# motor_driver.net
KiCad netlist of a schematic drawn in EAGLE
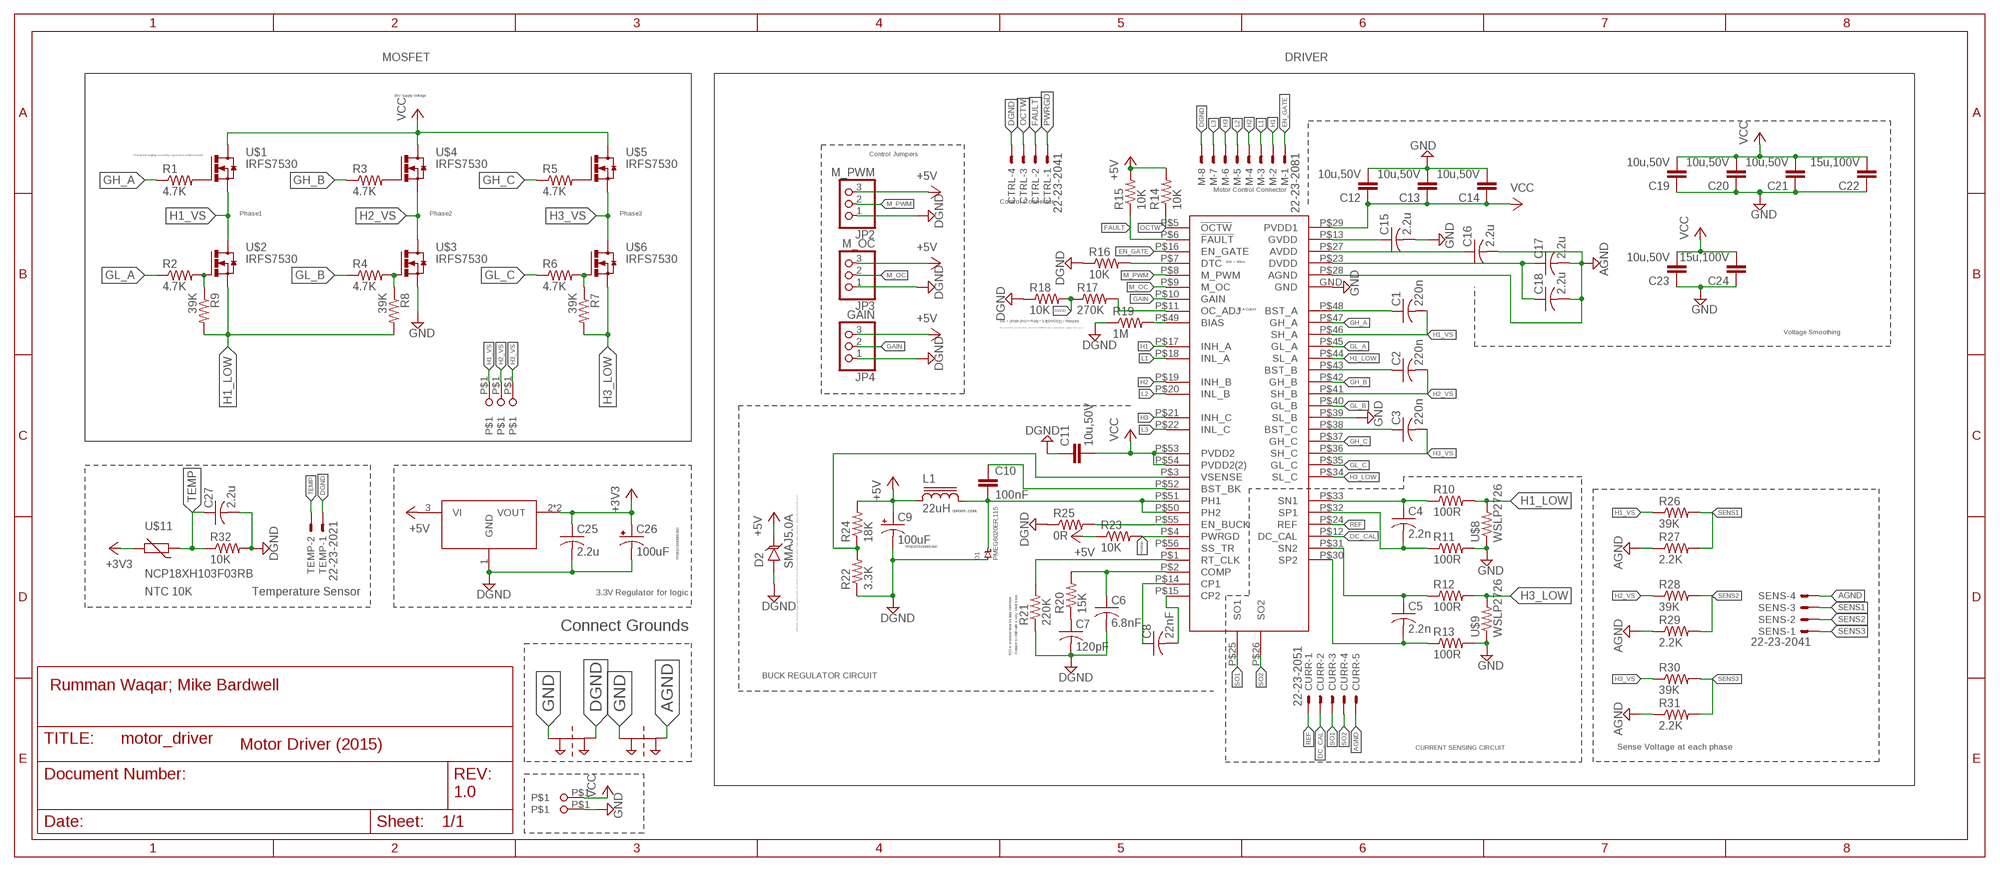
[diagram p0: schematic, sheet 1]

(export (version "E")
  (design (tool "Eeschema 10.0.6"))
  (components
    (comp (ref "C1")
      (value "220n")
      (footprint "eagle-import:C0805")
      (libsource (lib "eagle-import") (part "C-USC0805"))
    )
    (comp (ref "C2")
      (value "220n")
      (footprint "eagle-import:C0805")
      (libsource (lib "eagle-import") (part "C-USC0805"))
    )
    (comp (ref "C3")
      (value "220n")
      (footprint "eagle-import:C0805")
      (libsource (lib "eagle-import") (part "C-USC0805"))
    )
    (comp (ref "C4")
      (value "2.2n")
      (footprint "eagle-import:C0603")
      (libsource (lib "eagle-import") (part "C-USC0603"))
    )
    (comp (ref "C5")
      (value "2.2n")
      (footprint "eagle-import:C0603")
      (libsource (lib "eagle-import") (part "C-USC0603"))
    )
    (comp (ref "C6")
      (value "6.8nF")
      (footprint "eagle-import:C0603")
      (libsource (lib "eagle-import") (part "C-USC0603"))
    )
    (comp (ref "C7")
      (value "120pF")
      (footprint "eagle-import:C0603")
      (libsource (lib "eagle-import") (part "C-USC0603"))
    )
    (comp (ref "C8")
      (value "22nF")
      (footprint "eagle-import:C0603")
      (libsource (lib "eagle-import") (part "C-USC0603"))
    )
    (comp (ref "C9")
      (value "100uF")
      (footprint "eagle-import:EIA3528-KIT")
      (libsource (lib "eagle-import") (part "CAP_POL3528-KIT"))
    )
    (comp (ref "C10")
      (value "100nF")
      (footprint "eagle-import:0805")
      (libsource (lib "eagle-import") (part "CAP0805"))
    )
    (comp (ref "C11")
      (value "10u,50V")
      (footprint "eagle-import:1206")
      (libsource (lib "eagle-import") (part "CAP1206"))
    )
    (comp (ref "C12")
      (value "10u,50V")
      (footprint "eagle-import:1206")
      (libsource (lib "eagle-import") (part "CAP1206"))
    )
    (comp (ref "C13")
      (value "10u,50V")
      (footprint "eagle-import:1206")
      (libsource (lib "eagle-import") (part "CAP1206"))
    )
    (comp (ref "C14")
      (value "10u,50V")
      (footprint "eagle-import:1206")
      (libsource (lib "eagle-import") (part "CAP1206"))
    )
    (comp (ref "C15")
      (value "2.2u")
      (footprint "eagle-import:C0805")
      (libsource (lib "eagle-import") (part "C-USC0805"))
    )
    (comp (ref "C16")
      (value "2.2u")
      (footprint "eagle-import:C0805")
      (libsource (lib "eagle-import") (part "C-USC0805"))
    )
    (comp (ref "C17")
      (value "2.2u")
      (footprint "eagle-import:C0805")
      (libsource (lib "eagle-import") (part "C-USC0805"))
    )
    (comp (ref "C18")
      (value "2.2u")
      (footprint "eagle-import:C0805")
      (libsource (lib "eagle-import") (part "C-USC0805"))
    )
    (comp (ref "C19")
      (value "10u,50V")
      (footprint "eagle-import:1206")
      (libsource (lib "eagle-import") (part "CAP1206"))
    )
    (comp (ref "C20")
      (value "10u,50V")
      (footprint "eagle-import:1206")
      (libsource (lib "eagle-import") (part "CAP1206"))
    )
    (comp (ref "C21")
      (value "10u,50V")
      (footprint "eagle-import:1206")
      (libsource (lib "eagle-import") (part "CAP1206"))
    )
    (comp (ref "C22")
      (value "15u,100V")
      (footprint "eagle-import:C2220K")
      (libsource (lib "eagle-import") (part "C-EUC2220K"))
    )
    (comp (ref "C23")
      (value "10u,50V")
      (footprint "eagle-import:1206")
      (libsource (lib "eagle-import") (part "CAP1206"))
    )
    (comp (ref "C24")
      (value "15u,100V")
      (footprint "eagle-import:C2220K")
      (libsource (lib "eagle-import") (part "C-EUC2220K"))
    )
    (comp (ref "C25")
      (value "2.2u")
      (footprint "eagle-import:C0805")
      (libsource (lib "eagle-import") (part "C-USC0805"))
    )
    (comp (ref "C26")
      (value "100uF")
      (footprint "eagle-import:EIA3528-KIT")
      (libsource (lib "eagle-import") (part "CAP_POL3528-KIT"))
    )
    (comp (ref "C27")
      (value "2.2u")
      (footprint "eagle-import:C0805")
      (libsource (lib "eagle-import") (part "C-USC0805"))
    )
    (comp (ref "CTRL")
      (value "22-23-2041")
      (footprint "eagle-import:22-23-2041")
      (fields (field (name "MF") "MOLEX"))
      (libsource (lib "eagle-import") (part "22-23-2041"))
    )
    (comp (ref "CURR")
      (value "22-23-2051")
      (footprint "eagle-import:22-23-2051")
      (fields (field (name "MF") "MOLEX"))
      (libsource (lib "eagle-import") (part "22-23-2051"))
    )
    (comp (ref "D1")
      (value "PMEG6020ER,115")
      (footprint "eagle-import:SOD123W")
      (libsource (lib "eagle-import") (part "DIODE[SCHOTKY]-SOD123W"))
    )
    (comp (ref "D2")
      (value "SMAJ5.0A")
      (footprint "eagle-import:SMA-DIODE")
      (libsource (lib "eagle-import") (part "TVSSMA"))
    )
    (comp (ref "JP2")
      (value "M_PWM")
      (footprint "eagle-import:1X03")
      (libsource (lib "eagle-import") (part "PINHD-1X3"))
    )
    (comp (ref "JP3")
      (value "M_OC")
      (footprint "eagle-import:1X03")
      (libsource (lib "eagle-import") (part "PINHD-1X3"))
    )
    (comp (ref "JP4")
      (value "GAIN")
      (footprint "eagle-import:1X03")
      (libsource (lib "eagle-import") (part "PINHD-1X3"))
    )
    (comp (ref "L1")
      (value "22uH")
      (footprint "eagle-import:SDR0805")
      (libsource (lib "eagle-import") (part "SDR0805"))
    )
    (comp (ref "M")
      (value "22-23-2081")
      (footprint "eagle-import:22-23-2081")
      (fields (field (name "MF") "MOLEX"))
      (libsource (lib "eagle-import") (part "22-23-2081"))
    )
    (comp (ref "PT1")
      (value "2PT_GND_TIE")
      (footprint "eagle-import:2PT_GND_TIE")
      (libsource (lib "eagle-import") (part "2PT_GND_TIE"))
    )
    (comp (ref "PT2")
      (value "2PT_GND_TIE")
      (footprint "eagle-import:2PT_GND_TIE")
      (libsource (lib "eagle-import") (part "2PT_GND_TIE"))
    )
    (comp (ref "R1")
      (value "4.7K")
      (footprint "eagle-import:R0603")
      (libsource (lib "eagle-import") (part "R-US_R0603"))
    )
    (comp (ref "R2")
      (value "4.7K")
      (footprint "eagle-import:R0603")
      (libsource (lib "eagle-import") (part "R-US_R0603"))
    )
    (comp (ref "R3")
      (value "4.7K")
      (footprint "eagle-import:R0603")
      (libsource (lib "eagle-import") (part "R-US_R0603"))
    )
    (comp (ref "R4")
      (value "4.7K")
      (footprint "eagle-import:R0603")
      (libsource (lib "eagle-import") (part "R-US_R0603"))
    )
    (comp (ref "R5")
      (value "4.7K")
      (footprint "eagle-import:R0603")
      (libsource (lib "eagle-import") (part "R-US_R0603"))
    )
    (comp (ref "R6")
      (value "4.7K")
      (footprint "eagle-import:R0603")
      (libsource (lib "eagle-import") (part "R-US_R0603"))
    )
    (comp (ref "R7")
      (value "39K")
      (footprint "eagle-import:R0603")
      (libsource (lib "eagle-import") (part "R-US_R0603"))
    )
    (comp (ref "R8")
      (value "39K")
      (footprint "eagle-import:R0603")
      (libsource (lib "eagle-import") (part "R-US_R0603"))
    )
    (comp (ref "R9")
      (value "39K")
      (footprint "eagle-import:R0603")
      (libsource (lib "eagle-import") (part "R-US_R0603"))
    )
    (comp (ref "R10")
      (value "100R")
      (footprint "eagle-import:R0603")
      (libsource (lib "eagle-import") (part "R-US_R0603"))
    )
    (comp (ref "R11")
      (value "100R")
      (footprint "eagle-import:R0603")
      (libsource (lib "eagle-import") (part "R-US_R0603"))
    )
    (comp (ref "R12")
      (value "100R")
      (footprint "eagle-import:R0603")
      (libsource (lib "eagle-import") (part "R-US_R0603"))
    )
    (comp (ref "R13")
      (value "100R")
      (footprint "eagle-import:R0603")
      (libsource (lib "eagle-import") (part "R-US_R0603"))
    )
    (comp (ref "R14")
      (value "10K")
      (footprint "eagle-import:R0603")
      (libsource (lib "eagle-import") (part "R-US_R0603"))
    )
    (comp (ref "R15")
      (value "10K")
      (footprint "eagle-import:R0603")
      (libsource (lib "eagle-import") (part "R-US_R0603"))
    )
    (comp (ref "R16")
      (value "10K")
      (footprint "eagle-import:R0603")
      (libsource (lib "eagle-import") (part "R-US_R0603"))
    )
    (comp (ref "R17")
      (value "270K")
      (footprint "eagle-import:R0603")
      (libsource (lib "eagle-import") (part "R-US_R0603"))
    )
    (comp (ref "R18")
      (value "10K")
      (footprint "eagle-import:R0603")
      (libsource (lib "eagle-import") (part "R-US_R0603"))
    )
    (comp (ref "R19")
      (value "1M")
      (footprint "eagle-import:R0603")
      (libsource (lib "eagle-import") (part "R-US_R0603"))
    )
    (comp (ref "R20")
      (value "15K")
      (footprint "eagle-import:R0603")
      (libsource (lib "eagle-import") (part "R-US_R0603"))
    )
    (comp (ref "R21")
      (value "220K")
      (footprint "eagle-import:R0603")
      (libsource (lib "eagle-import") (part "R-US_R0603"))
    )
    (comp (ref "R22")
      (value "3.3K")
      (footprint "eagle-import:R0603")
      (libsource (lib "eagle-import") (part "R-US_R0603"))
    )
    (comp (ref "R23")
      (value "10K")
      (footprint "eagle-import:R0603")
      (libsource (lib "eagle-import") (part "R-US_R0603"))
    )
    (comp (ref "R24")
      (value "18K")
      (footprint "eagle-import:R0603")
      (libsource (lib "eagle-import") (part "R-US_R0603"))
    )
    (comp (ref "R25")
      (value "0R")
      (footprint "eagle-import:R0603")
      (libsource (lib "eagle-import") (part "R-US_R0603"))
    )
    (comp (ref "R26")
      (value "39K")
      (footprint "eagle-import:R0805")
      (libsource (lib "eagle-import") (part "R-US_R0805"))
    )
    (comp (ref "R27")
      (value "2.2K")
      (footprint "eagle-import:R0805")
      (libsource (lib "eagle-import") (part "R-US_R0805"))
    )
    (comp (ref "R28")
      (value "39K")
      (footprint "eagle-import:R0805")
      (libsource (lib "eagle-import") (part "R-US_R0805"))
    )
    (comp (ref "R29")
      (value "2.2K")
      (footprint "eagle-import:R0805")
      (libsource (lib "eagle-import") (part "R-US_R0805"))
    )
    (comp (ref "R30")
      (value "39K")
      (footprint "eagle-import:R0805")
      (libsource (lib "eagle-import") (part "R-US_R0805"))
    )
    (comp (ref "R31")
      (value "2.2K")
      (footprint "eagle-import:R0805")
      (libsource (lib "eagle-import") (part "R-US_R0805"))
    )
    (comp (ref "R32")
      (value "10K")
      (footprint "eagle-import:M0805")
      (libsource (lib "eagle-import") (part "R-US_M0805"))
    )
    (comp (ref "SENS")
      (value "22-23-2041")
      (footprint "eagle-import:22-23-2041")
      (fields (field (name "MF") "MOLEX"))
      (libsource (lib "eagle-import") (part "22-23-2041"))
    )
    (comp (ref "TEMP")
      (value "22-23-2021")
      (footprint "eagle-import:22-23-2021")
      (fields (field (name "MF") "MOLEX"))
      (libsource (lib "eagle-import") (part "22-23-2021"))
    )
    (comp (ref "U$1")
      (value "IRFS7530")
      (footprint "eagle-import:IRF7530_HEATSINK")
      (libsource (lib "eagle-import") (part "IRFS7530_HEATSINK"))
    )
    (comp (ref "U$2")
      (value "IRFS7530")
      (footprint "eagle-import:IRF7530_HEATSINK")
      (libsource (lib "eagle-import") (part "IRFS7530_HEATSINK"))
    )
    (comp (ref "U$3")
      (value "IRFS7530")
      (footprint "eagle-import:IRF7530_HEATSINK")
      (libsource (lib "eagle-import") (part "IRFS7530_HEATSINK"))
    )
    (comp (ref "U$4")
      (value "IRFS7530")
      (footprint "eagle-import:IRF7530_HEATSINK")
      (libsource (lib "eagle-import") (part "IRFS7530_HEATSINK"))
    )
    (comp (ref "U$5")
      (value "IRFS7530")
      (footprint "eagle-import:IRF7530_HEATSINK")
      (libsource (lib "eagle-import") (part "IRFS7530_HEATSINK"))
    )
    (comp (ref "U$6")
      (value "IRFS7530")
      (footprint "eagle-import:IRF7530_HEATSINK")
      (libsource (lib "eagle-import") (part "IRFS7530_HEATSINK"))
    )
    (comp (ref "U$7")
      (value "DRV8302")
      (footprint "eagle-import:DRV8302")
      (libsource (lib "eagle-import") (part "DRV8302"))
    )
    (comp (ref "U$8")
      (value "WSLP2726")
      (footprint "eagle-import:WSLP2726")
      (libsource (lib "eagle-import") (part "WSLP2726"))
    )
    (comp (ref "U$9")
      (value "WSLP2726")
      (footprint "eagle-import:WSLP2726")
      (libsource (lib "eagle-import") (part "WSLP2726"))
    )
    (comp (ref "U$10")
      (value "TC2117")
      (footprint "eagle-import:SOT223")
      (libsource (lib "eagle-import") (part "TC2117"))
    )
    (comp (ref "U$11")
      (value "NCP18XH103F03RB")
      (footprint "eagle-import:R0603")
      (libsource (lib "eagle-import") (part "NCP18XH103F03RB"))
    )
    (comp (ref "U$12")
      (value "1CONN_SOLDER")
      (footprint "eagle-import:1CONN_PAD")
      (libsource (lib "eagle-import") (part "1CONN_SOLDER"))
    )
    (comp (ref "U$13")
      (value "1CONN_SOLDER")
      (footprint "eagle-import:1CONN_PAD")
      (libsource (lib "eagle-import") (part "1CONN_SOLDER"))
    )
    (comp (ref "U$14")
      (value "1CONN_SOLDER")
      (footprint "eagle-import:1CONN_PAD")
      (libsource (lib "eagle-import") (part "1CONN_SOLDER"))
    )
    (comp (ref "U$15")
      (value "1CONN_SOLDER")
      (footprint "eagle-import:1CONN_PAD")
      (libsource (lib "eagle-import") (part "1CONN_SOLDER"))
    )
    (comp (ref "U$16")
      (value "1CONN_SOLDER")
      (footprint "eagle-import:1CONN_PAD")
      (libsource (lib "eagle-import") (part "1CONN_SOLDER"))
    )
  )
  (nets
    (net (code "1") (name "+3V3") (class "Default")
      (node (ref "C25") (pin "1") (pinfunction "1_1") (pintype "passive"))
      (node (ref "C26") (pin "A") (pinfunction "+_A") (pintype "passive"))
      (node (ref "U$10") (pin "2") (pinfunction "VOUT_2") (pintype "bidirectional"))
      (node (ref "U$10") (pin "4") (pinfunction "VOUT_4") (pintype "bidirectional"))
      (node (ref "U$11") (pin "2") (pinfunction "2_2") (pintype "passive"))
    )
    (net (code "2") (name "+5V") (class "Default")
      (node (ref "C9") (pin "A") (pinfunction "+_A") (pintype "passive"))
      (node (ref "D2") (pin "C") (pinfunction "C_C") (pintype "passive"))
      (node (ref "JP2") (pin "3") (pinfunction "3_3") (pintype "passive"))
      (node (ref "JP3") (pin "3") (pinfunction "3_3") (pintype "passive"))
      (node (ref "JP4") (pin "3") (pinfunction "3_3") (pintype "passive"))
      (node (ref "L1") (pin "1") (pinfunction "1_1") (pintype "passive"))
      (node (ref "R14") (pin "2") (pinfunction "2_2") (pintype "passive"))
      (node (ref "R15") (pin "2") (pinfunction "2_2") (pintype "passive"))
      (node (ref "R23") (pin "1") (pinfunction "1_1") (pintype "passive"))
      (node (ref "R24") (pin "2") (pinfunction "2_2") (pintype "passive"))
      (node (ref "U$10") (pin "3") (pinfunction "VI_3") (pintype "bidirectional"))
    )
    (net (code "3") (name "AGND") (class "Default")
      (node (ref "C16") (pin "2") (pinfunction "2_2") (pintype "passive"))
      (node (ref "C17") (pin "2") (pinfunction "2_2") (pintype "passive"))
      (node (ref "C18") (pin "2") (pinfunction "2_2") (pintype "passive"))
      (node (ref "CURR") (pin "5") (pinfunction "S_5") (pintype "passive"))
      (node (ref "PT2") (pin "P$2") (pinfunction "P$2_P$2") (pintype "bidirectional"))
      (node (ref "R27") (pin "1") (pinfunction "1_1") (pintype "passive"))
      (node (ref "R29") (pin "1") (pinfunction "1_1") (pintype "passive"))
      (node (ref "R31") (pin "1") (pinfunction "1_1") (pintype "passive"))
      (node (ref "SENS") (pin "4") (pinfunction "S_4") (pintype "passive"))
      (node (ref "U$7") (pin "P$28") (pinfunction "AGND_P$28") (pintype "bidirectional"))
    )
    (net (code "4") (name "DC_CAL") (class "Default")
      (node (ref "CURR") (pin "2") (pinfunction "S_2") (pintype "passive"))
      (node (ref "U$7") (pin "P$12") (pinfunction "DC_CAL_P$12") (pintype "bidirectional"))
    )
    (net (code "5") (name "DGND") (class "Default")
      (node (ref "C11") (pin "1") (pinfunction "1_1") (pintype "passive"))
      (node (ref "C25") (pin "2") (pinfunction "2_2") (pintype "passive"))
      (node (ref "C26") (pin "C") (pinfunction "-_C") (pintype "passive"))
      (node (ref "C27") (pin "2") (pinfunction "2_2") (pintype "passive"))
      (node (ref "C6") (pin "2") (pinfunction "2_2") (pintype "passive"))
      (node (ref "C7") (pin "2") (pinfunction "2_2") (pintype "passive"))
      (node (ref "C9") (pin "C") (pinfunction "-_C") (pintype "passive"))
      (node (ref "CTRL") (pin "4") (pinfunction "S_4") (pintype "passive"))
      (node (ref "D1") (pin "P$1") (pinfunction "1_P$1") (pintype "bidirectional"))
      (node (ref "D2") (pin "A") (pinfunction "A_A") (pintype "passive"))
      (node (ref "JP2") (pin "1") (pinfunction "1_1") (pintype "passive"))
      (node (ref "JP3") (pin "1") (pinfunction "1_1") (pintype "passive"))
      (node (ref "JP4") (pin "1") (pinfunction "1_1") (pintype "passive"))
      (node (ref "M") (pin "8") (pinfunction "S_8") (pintype "passive"))
      (node (ref "PT1") (pin "P$2") (pinfunction "P$2_P$2") (pintype "bidirectional"))
      (node (ref "R16") (pin "1") (pinfunction "1_1") (pintype "passive"))
      (node (ref "R18") (pin "1") (pinfunction "1_1") (pintype "passive"))
      (node (ref "R19") (pin "1") (pinfunction "1_1") (pintype "passive"))
      (node (ref "R21") (pin "1") (pinfunction "1_1") (pintype "passive"))
      (node (ref "R22") (pin "1") (pinfunction "1_1") (pintype "passive"))
      (node (ref "R25") (pin "1") (pinfunction "1_1") (pintype "passive"))
      (node (ref "R32") (pin "2") (pinfunction "2_2") (pintype "passive"))
      (node (ref "TEMP") (pin "1") (pinfunction "S_1") (pintype "passive"))
      (node (ref "U$10") (pin "1") (pinfunction "GND_1") (pintype "bidirectional"))
    )
    (net (code "6") (name "DVDD") (class "Default")
      (node (ref "R17") (pin "1") (pinfunction "1_1") (pintype "passive"))
      (node (ref "R18") (pin "2") (pinfunction "2_2") (pintype "passive"))
    )
    (net (code "7") (name "EN_GATE") (class "Default")
      (node (ref "M") (pin "1") (pinfunction "S_1") (pintype "passive"))
      (node (ref "U$7") (pin "P$16") (pinfunction "EN_GATE_P$16") (pintype "bidirectional"))
    )
    (net (code "8") (name "FAULT") (class "Default")
      (node (ref "CTRL") (pin "2") (pinfunction "S_2") (pintype "passive"))
      (node (ref "R15") (pin "1") (pinfunction "1_1") (pintype "passive"))
      (node (ref "U$7") (pin "P$6") (pinfunction "~{FAULT}_P$6") (pintype "bidirectional"))
    )
    (net (code "9") (name "GAIN") (class "Default")
      (node (ref "JP4") (pin "2") (pinfunction "2_2") (pintype "passive"))
      (node (ref "U$7") (pin "P$10") (pinfunction "GAIN_P$10") (pintype "bidirectional"))
    )
    (net (code "10") (name "GH_A") (class "Default")
      (node (ref "R1") (pin "1") (pinfunction "1_1") (pintype "passive"))
      (node (ref "U$7") (pin "P$47") (pinfunction "GH_A_P$47") (pintype "bidirectional"))
    )
    (net (code "11") (name "GH_B") (class "Default")
      (node (ref "R3") (pin "1") (pinfunction "1_1") (pintype "passive"))
      (node (ref "U$7") (pin "P$42") (pinfunction "GH_B_P$42") (pintype "bidirectional"))
    )
    (net (code "12") (name "GH_C") (class "Default")
      (node (ref "R5") (pin "1") (pinfunction "1_1") (pintype "passive"))
      (node (ref "U$7") (pin "P$37") (pinfunction "GH_C_P$37") (pintype "bidirectional"))
    )
    (net (code "13") (name "GL_A") (class "Default")
      (node (ref "R2") (pin "1") (pinfunction "1_1") (pintype "passive"))
      (node (ref "U$7") (pin "P$45") (pinfunction "GL_A_P$45") (pintype "bidirectional"))
    )
    (net (code "14") (name "GL_B") (class "Default")
      (node (ref "R4") (pin "1") (pinfunction "1_1") (pintype "passive"))
      (node (ref "U$7") (pin "P$40") (pinfunction "GL_B_P$40") (pintype "bidirectional"))
    )
    (net (code "15") (name "GL_C") (class "Default")
      (node (ref "R6") (pin "1") (pinfunction "1_1") (pintype "passive"))
      (node (ref "U$7") (pin "P$35") (pinfunction "GL_C_P$35") (pintype "bidirectional"))
    )
    (net (code "16") (name "GND") (class "Default")
      (node (ref "C12") (pin "2") (pinfunction "2_2") (pintype "passive"))
      (node (ref "C13") (pin "2") (pinfunction "2_2") (pintype "passive"))
      (node (ref "C14") (pin "2") (pinfunction "2_2") (pintype "passive"))
      (node (ref "C15") (pin "2") (pinfunction "2_2") (pintype "passive"))
      (node (ref "C19") (pin "1") (pinfunction "1_1") (pintype "passive"))
      (node (ref "C20") (pin "1") (pinfunction "1_1") (pintype "passive"))
      (node (ref "C21") (pin "1") (pinfunction "1_1") (pintype "passive"))
      (node (ref "C22") (pin "1") (pinfunction "1_1") (pintype "passive"))
      (node (ref "C23") (pin "1") (pinfunction "1_1") (pintype "passive"))
      (node (ref "C24") (pin "1") (pinfunction "1_1") (pintype "passive"))
      (node (ref "PT1") (pin "P$1") (pinfunction "P$1_P$1") (pintype "bidirectional"))
      (node (ref "PT2") (pin "P$1") (pinfunction "P$1_P$1") (pintype "bidirectional"))
      (node (ref "R11") (pin "2") (pinfunction "2_2") (pintype "passive"))
      (node (ref "R13") (pin "2") (pinfunction "2_2") (pintype "passive"))
      (node (ref "U$16") (pin "P$1") (pinfunction "P$1_P$1") (pintype "bidirectional"))
      (node (ref "U$3") (pin "S1") (pinfunction "S_S1") (pintype "passive"))
      (node (ref "U$3") (pin "S2") (pinfunction "S_S2") (pintype "passive"))
      (node (ref "U$3") (pin "S3") (pinfunction "S_S3") (pintype "passive"))
      (node (ref "U$3") (pin "S4") (pinfunction "S_S4") (pintype "passive"))
      (node (ref "U$3") (pin "S5") (pinfunction "S_S5") (pintype "passive"))
      (node (ref "U$7") (pin "GND") (pinfunction "GND_GND") (pintype "bidirectional"))
      (node (ref "U$7") (pin "P$39") (pinfunction "SL_B_P$39") (pintype "bidirectional"))
      (node (ref "U$8") (pin "P$1@1") (pinfunction "1_P$1@1") (pintype "passive"))
      (node (ref "U$8") (pin "P$1@2") (pinfunction "1_P$1@2") (pintype "passive"))
      (node (ref "U$9") (pin "P$1@1") (pinfunction "1_P$1@1") (pintype "passive"))
      (node (ref "U$9") (pin "P$1@2") (pinfunction "1_P$1@2") (pintype "passive"))
    )
    (net (code "17") (name "H1") (class "Default")
      (node (ref "M") (pin "2") (pinfunction "S_2") (pintype "passive"))
      (node (ref "U$7") (pin "P$17") (pinfunction "INH_A_P$17") (pintype "bidirectional"))
    )
    (net (code "18") (name "H1_LOW") (class "Default")
      (node (ref "R10") (pin "2") (pinfunction "2_2") (pintype "passive"))
      (node (ref "R8") (pin "2") (pinfunction "2_2") (pintype "passive"))
      (node (ref "R9") (pin "2") (pinfunction "2_2") (pintype "passive"))
      (node (ref "U$2") (pin "S1") (pinfunction "S_S1") (pintype "passive"))
      (node (ref "U$2") (pin "S2") (pinfunction "S_S2") (pintype "passive"))
      (node (ref "U$2") (pin "S3") (pinfunction "S_S3") (pintype "passive"))
      (node (ref "U$2") (pin "S4") (pinfunction "S_S4") (pintype "passive"))
      (node (ref "U$2") (pin "S5") (pinfunction "S_S5") (pintype "passive"))
      (node (ref "U$7") (pin "P$44") (pinfunction "SL_A_P$44") (pintype "bidirectional"))
      (node (ref "U$8") (pin "P$2@1") (pinfunction "2_P$2@1") (pintype "passive"))
      (node (ref "U$8") (pin "P$2@2") (pinfunction "2_P$2@2") (pintype "passive"))
    )
    (net (code "19") (name "H1_VS") (class "Default")
      (node (ref "C1") (pin "2") (pinfunction "2_2") (pintype "passive"))
      (node (ref "R26") (pin "1") (pinfunction "1_1") (pintype "passive"))
      (node (ref "U$1") (pin "S1") (pinfunction "S_S1") (pintype "passive"))
      (node (ref "U$1") (pin "S2") (pinfunction "S_S2") (pintype "passive"))
      (node (ref "U$1") (pin "S3") (pinfunction "S_S3") (pintype "passive"))
      (node (ref "U$1") (pin "S4") (pinfunction "S_S4") (pintype "passive"))
      (node (ref "U$1") (pin "S5") (pinfunction "S_S5") (pintype "passive"))
      (node (ref "U$14") (pin "P$1") (pinfunction "P$1_P$1") (pintype "bidirectional"))
      (node (ref "U$2") (pin "D1") (pinfunction "D_D1") (pintype "passive"))
      (node (ref "U$7") (pin "P$46") (pinfunction "SH_A_P$46") (pintype "bidirectional"))
    )
    (net (code "20") (name "H2") (class "Default")
      (node (ref "M") (pin "4") (pinfunction "S_4") (pintype "passive"))
      (node (ref "U$7") (pin "P$19") (pinfunction "INH_B_P$19") (pintype "bidirectional"))
    )
    (net (code "21") (name "H2_VS") (class "Default")
      (node (ref "C2") (pin "2") (pinfunction "2_2") (pintype "passive"))
      (node (ref "R28") (pin "1") (pinfunction "1_1") (pintype "passive"))
      (node (ref "U$13") (pin "P$1") (pinfunction "P$1_P$1") (pintype "bidirectional"))
      (node (ref "U$3") (pin "D1") (pinfunction "D_D1") (pintype "passive"))
      (node (ref "U$4") (pin "S1") (pinfunction "S_S1") (pintype "passive"))
      (node (ref "U$4") (pin "S2") (pinfunction "S_S2") (pintype "passive"))
      (node (ref "U$4") (pin "S3") (pinfunction "S_S3") (pintype "passive"))
      (node (ref "U$4") (pin "S4") (pinfunction "S_S4") (pintype "passive"))
      (node (ref "U$4") (pin "S5") (pinfunction "S_S5") (pintype "passive"))
      (node (ref "U$7") (pin "P$41") (pinfunction "SH_B_P$41") (pintype "bidirectional"))
    )
    (net (code "22") (name "H3") (class "Default")
      (node (ref "M") (pin "6") (pinfunction "S_6") (pintype "passive"))
      (node (ref "U$7") (pin "P$21") (pinfunction "INH_C_P$21") (pintype "bidirectional"))
    )
    (net (code "23") (name "H3_LOW") (class "Default")
      (node (ref "R12") (pin "2") (pinfunction "2_2") (pintype "passive"))
      (node (ref "R7") (pin "2") (pinfunction "2_2") (pintype "passive"))
      (node (ref "U$6") (pin "S1") (pinfunction "S_S1") (pintype "passive"))
      (node (ref "U$6") (pin "S2") (pinfunction "S_S2") (pintype "passive"))
      (node (ref "U$6") (pin "S3") (pinfunction "S_S3") (pintype "passive"))
      (node (ref "U$6") (pin "S4") (pinfunction "S_S4") (pintype "passive"))
      (node (ref "U$6") (pin "S5") (pinfunction "S_S5") (pintype "passive"))
      (node (ref "U$7") (pin "P$34") (pinfunction "SL_C_P$34") (pintype "bidirectional"))
      (node (ref "U$9") (pin "P$2@1") (pinfunction "2_P$2@1") (pintype "passive"))
      (node (ref "U$9") (pin "P$2@2") (pinfunction "2_P$2@2") (pintype "passive"))
    )
    (net (code "24") (name "H3_VS") (class "Default")
      (node (ref "C3") (pin "2") (pinfunction "2_2") (pintype "passive"))
      (node (ref "R30") (pin "1") (pinfunction "1_1") (pintype "passive"))
      (node (ref "U$12") (pin "P$1") (pinfunction "P$1_P$1") (pintype "bidirectional"))
      (node (ref "U$5") (pin "S1") (pinfunction "S_S1") (pintype "passive"))
      (node (ref "U$5") (pin "S2") (pinfunction "S_S2") (pintype "passive"))
      (node (ref "U$5") (pin "S3") (pinfunction "S_S3") (pintype "passive"))
      (node (ref "U$5") (pin "S4") (pinfunction "S_S4") (pintype "passive"))
      (node (ref "U$5") (pin "S5") (pinfunction "S_S5") (pintype "passive"))
      (node (ref "U$6") (pin "D1") (pinfunction "D_D1") (pintype "passive"))
      (node (ref "U$7") (pin "P$36") (pinfunction "SH_C_P$36") (pintype "bidirectional"))
    )
    (net (code "25") (name "L1") (class "Default")
      (node (ref "M") (pin "3") (pinfunction "S_3") (pintype "passive"))
      (node (ref "U$7") (pin "P$18") (pinfunction "INL_A_P$18") (pintype "bidirectional"))
    )
    (net (code "26") (name "L2") (class "Default")
      (node (ref "M") (pin "5") (pinfunction "S_5") (pintype "passive"))
      (node (ref "U$7") (pin "P$20") (pinfunction "INL_B_P$20") (pintype "bidirectional"))
    )
    (net (code "27") (name "L3") (class "Default")
      (node (ref "M") (pin "7") (pinfunction "S_7") (pintype "passive"))
      (node (ref "U$7") (pin "P$22") (pinfunction "INL_C_P$22") (pintype "bidirectional"))
    )
    (net (code "28") (name "M_OC") (class "Default")
      (node (ref "JP3") (pin "2") (pinfunction "2_2") (pintype "passive"))
      (node (ref "U$7") (pin "P$9") (pinfunction "M_OC_P$9") (pintype "bidirectional"))
    )
    (net (code "29") (name "M_PWM") (class "Default")
      (node (ref "JP2") (pin "2") (pinfunction "2_2") (pintype "passive"))
      (node (ref "U$7") (pin "P$8") (pinfunction "M_PWM_P$8") (pintype "bidirectional"))
    )
    (net (code "30") (name "Net-(C7-Pad1)") (class "Default")
      (node (ref "C7") (pin "1") (pinfunction "1_1") (pintype "passive"))
      (node (ref "R20") (pin "1") (pinfunction "1_1") (pintype "passive"))
    )
    (net (code "31") (name "Net-(D1-2)") (class "Default")
      (node (ref "C10") (pin "2") (pinfunction "2_2") (pintype "passive"))
      (node (ref "D1") (pin "P$2") (pinfunction "2_P$2") (pintype "bidirectional"))
      (node (ref "L1") (pin "2") (pinfunction "2_2") (pintype "passive"))
      (node (ref "U$7") (pin "P$50") (pinfunction "PH2_P$50") (pintype "bidirectional"))
      (node (ref "U$7") (pin "P$51") (pinfunction "PH1_P$51") (pintype "bidirectional"))
    )
    (net (code "32") (name "Net-(U$1-G)") (class "Default")
      (node (ref "R1") (pin "2") (pinfunction "2_2") (pintype "passive"))
      (node (ref "U$1") (pin "G1") (pinfunction "G_G1") (pintype "passive"))
    )
    (net (code "33") (name "Net-(U$2-G)") (class "Default")
      (node (ref "R2") (pin "2") (pinfunction "2_2") (pintype "passive"))
      (node (ref "R9") (pin "1") (pinfunction "1_1") (pintype "passive"))
      (node (ref "U$2") (pin "G1") (pinfunction "G_G1") (pintype "passive"))
    )
    (net (code "34") (name "Net-(U$3-G)") (class "Default")
      (node (ref "R4") (pin "2") (pinfunction "2_2") (pintype "passive"))
      (node (ref "R8") (pin "1") (pinfunction "1_1") (pintype "passive"))
      (node (ref "U$3") (pin "G1") (pinfunction "G_G1") (pintype "passive"))
    )
    (net (code "35") (name "Net-(U$4-G)") (class "Default")
      (node (ref "R3") (pin "2") (pinfunction "2_2") (pintype "passive"))
      (node (ref "U$4") (pin "G1") (pinfunction "G_G1") (pintype "passive"))
    )
    (net (code "36") (name "Net-(U$5-G)") (class "Default")
      (node (ref "R5") (pin "2") (pinfunction "2_2") (pintype "passive"))
      (node (ref "U$5") (pin "G1") (pinfunction "G_G1") (pintype "passive"))
    )
    (net (code "37") (name "Net-(U$6-G)") (class "Default")
      (node (ref "R6") (pin "2") (pinfunction "2_2") (pintype "passive"))
      (node (ref "R7") (pin "1") (pinfunction "1_1") (pintype "passive"))
      (node (ref "U$6") (pin "G1") (pinfunction "G_G1") (pintype "passive"))
    )
    (net (code "38") (name "Net-(U$7-AVDD)") (class "Default")
      (node (ref "C16") (pin "1") (pinfunction "1_1") (pintype "passive"))
      (node (ref "U$7") (pin "P$27") (pinfunction "AVDD_P$27") (pintype "bidirectional"))
    )
    (net (code "39") (name "Net-(U$7-BIAS)") (class "Default")
      (node (ref "R19") (pin "2") (pinfunction "2_2") (pintype "passive"))
      (node (ref "U$7") (pin "P$49") (pinfunction "BIAS_P$49") (pintype "bidirectional"))
    )
    (net (code "40") (name "Net-(U$7-BST_A)") (class "Default")
      (node (ref "C1") (pin "1") (pinfunction "1_1") (pintype "passive"))
      (node (ref "U$7") (pin "P$48") (pinfunction "BST_A_P$48") (pintype "bidirectional"))
    )
    (net (code "41") (name "Net-(U$7-BST_B)") (class "Default")
      (node (ref "C2") (pin "1") (pinfunction "1_1") (pintype "passive"))
      (node (ref "U$7") (pin "P$43") (pinfunction "BST_B_P$43") (pintype "bidirectional"))
    )
    (net (code "42") (name "Net-(U$7-BST_BK)") (class "Default")
      (node (ref "C10") (pin "1") (pinfunction "1_1") (pintype "passive"))
      (node (ref "U$7") (pin "P$52") (pinfunction "BST_BK_P$52") (pintype "bidirectional"))
    )
    (net (code "43") (name "Net-(U$7-BST_C)") (class "Default")
      (node (ref "C3") (pin "1") (pinfunction "1_1") (pintype "passive"))
      (node (ref "U$7") (pin "P$38") (pinfunction "BST_C_P$38") (pintype "bidirectional"))
    )
    (net (code "44") (name "Net-(U$7-COMP)") (class "Default")
      (node (ref "C6") (pin "1") (pinfunction "1_1") (pintype "passive"))
      (node (ref "R20") (pin "2") (pinfunction "2_2") (pintype "passive"))
      (node (ref "U$7") (pin "P$2") (pinfunction "COMP_P$2") (pintype "bidirectional"))
    )
    (net (code "45") (name "Net-(U$7-CP1)") (class "Default")
      (node (ref "C8") (pin "1") (pinfunction "1_1") (pintype "passive"))
      (node (ref "U$7") (pin "P$14") (pinfunction "CP1_P$14") (pintype "bidirectional"))
    )
    (net (code "46") (name "Net-(U$7-CP2)") (class "Default")
      (node (ref "C8") (pin "2") (pinfunction "2_2") (pintype "passive"))
      (node (ref "U$7") (pin "P$15") (pinfunction "CP2_P$15") (pintype "bidirectional"))
    )
    (net (code "47") (name "Net-(U$7-DTC)") (class "Default")
      (node (ref "R16") (pin "2") (pinfunction "2_2") (pintype "passive"))
      (node (ref "U$7") (pin "P$7") (pinfunction "DTC_P$7") (pintype "bidirectional"))
    )
    (net (code "48") (name "Net-(U$7-DVDD)") (class "Default")
      (node (ref "C17") (pin "1") (pinfunction "1_1") (pintype "passive"))
      (node (ref "C18") (pin "1") (pinfunction "1_1") (pintype "passive"))
      (node (ref "U$7") (pin "P$23") (pinfunction "DVDD_P$23") (pintype "bidirectional"))
    )
    (net (code "49") (name "Net-(U$7-EN_BUCK)") (class "Default")
      (node (ref "R25") (pin "2") (pinfunction "2_2") (pintype "passive"))
      (node (ref "U$7") (pin "P$55") (pinfunction "EN_BUCK_P$55") (pintype "bidirectional"))
    )
    (net (code "50") (name "Net-(U$7-GVDD)") (class "Default")
      (node (ref "C15") (pin "1") (pinfunction "1_1") (pintype "passive"))
      (node (ref "U$7") (pin "P$13") (pinfunction "GVDD_P$13") (pintype "bidirectional"))
    )
    (net (code "51") (name "Net-(U$7-OC_ADJ)") (class "Default")
      (node (ref "R17") (pin "2") (pinfunction "2_2") (pintype "passive"))
      (node (ref "U$7") (pin "P$11") (pinfunction "OC_ADJ_P$11") (pintype "bidirectional"))
    )
    (net (code "52") (name "Net-(U$7-RT_CLK)") (class "Default")
      (node (ref "R21") (pin "2") (pinfunction "2_2") (pintype "passive"))
      (node (ref "U$7") (pin "P$1") (pinfunction "RT_CLK_P$1") (pintype "bidirectional"))
    )
    (net (code "53") (name "Net-(U$7-SN1)") (class "Default")
      (node (ref "C4") (pin "1") (pinfunction "1_1") (pintype "passive"))
      (node (ref "R10") (pin "1") (pinfunction "1_1") (pintype "passive"))
      (node (ref "U$7") (pin "P$33") (pinfunction "SN1_P$33") (pintype "bidirectional"))
    )
    (net (code "54") (name "Net-(U$7-SN2)") (class "Default")
      (node (ref "C5") (pin "1") (pinfunction "1_1") (pintype "passive"))
      (node (ref "R12") (pin "1") (pinfunction "1_1") (pintype "passive"))
      (node (ref "U$7") (pin "P$31") (pinfunction "SN2_P$31") (pintype "bidirectional"))
    )
    (net (code "55") (name "Net-(U$7-SP1)") (class "Default")
      (node (ref "C4") (pin "2") (pinfunction "2_2") (pintype "passive"))
      (node (ref "R11") (pin "1") (pinfunction "1_1") (pintype "passive"))
      (node (ref "U$7") (pin "P$32") (pinfunction "SP1_P$32") (pintype "bidirectional"))
    )
    (net (code "56") (name "Net-(U$7-SP2)") (class "Default")
      (node (ref "C5") (pin "2") (pinfunction "2_2") (pintype "passive"))
      (node (ref "R13") (pin "1") (pinfunction "1_1") (pintype "passive"))
      (node (ref "U$7") (pin "P$30") (pinfunction "SP2_P$30") (pintype "bidirectional"))
    )
    (net (code "57") (name "Net-(U$7-VSENSE)") (class "Default")
      (node (ref "R22") (pin "2") (pinfunction "2_2") (pintype "passive"))
      (node (ref "R24") (pin "1") (pinfunction "1_1") (pintype "passive"))
      (node (ref "U$7") (pin "P$3") (pinfunction "VSENSE_P$3") (pintype "bidirectional"))
    )
    (net (code "58") (name "OCTW") (class "Default")
      (node (ref "CTRL") (pin "3") (pinfunction "S_3") (pintype "passive"))
      (node (ref "R14") (pin "1") (pinfunction "1_1") (pintype "passive"))
      (node (ref "U$7") (pin "P$5") (pinfunction "~{OCTW}_P$5") (pintype "bidirectional"))
    )
    (net (code "59") (name "PWRGD") (class "Default")
      (node (ref "CTRL") (pin "1") (pinfunction "S_1") (pintype "passive"))
      (node (ref "R23") (pin "2") (pinfunction "2_2") (pintype "passive"))
      (node (ref "U$7") (pin "P$4") (pinfunction "PWRGD_P$4") (pintype "bidirectional"))
    )
    (net (code "60") (name "REF") (class "Default")
      (node (ref "CURR") (pin "1") (pinfunction "S_1") (pintype "passive"))
      (node (ref "U$7") (pin "P$24") (pinfunction "REF_P$24") (pintype "bidirectional"))
    )
    (net (code "61") (name "SENS1") (class "Default")
      (node (ref "R26") (pin "2") (pinfunction "2_2") (pintype "passive"))
      (node (ref "R27") (pin "2") (pinfunction "2_2") (pintype "passive"))
      (node (ref "SENS") (pin "3") (pinfunction "S_3") (pintype "passive"))
    )
    (net (code "62") (name "SENS2") (class "Default")
      (node (ref "R28") (pin "2") (pinfunction "2_2") (pintype "passive"))
      (node (ref "R29") (pin "2") (pinfunction "2_2") (pintype "passive"))
      (node (ref "SENS") (pin "2") (pinfunction "S_2") (pintype "passive"))
    )
    (net (code "63") (name "SENS3") (class "Default")
      (node (ref "R30") (pin "2") (pinfunction "2_2") (pintype "passive"))
      (node (ref "R31") (pin "2") (pinfunction "2_2") (pintype "passive"))
      (node (ref "SENS") (pin "1") (pinfunction "S_1") (pintype "passive"))
    )
    (net (code "64") (name "SO1") (class "Default")
      (node (ref "CURR") (pin "3") (pinfunction "S_3") (pintype "passive"))
      (node (ref "U$7") (pin "P$25") (pinfunction "SO1_P$25") (pintype "bidirectional"))
    )
    (net (code "65") (name "SO2") (class "Default")
      (node (ref "CURR") (pin "4") (pinfunction "S_4") (pintype "passive"))
      (node (ref "U$7") (pin "P$26") (pinfunction "SO2_P$26") (pintype "bidirectional"))
    )
    (net (code "66") (name "TEMP") (class "Default")
      (node (ref "C27") (pin "1") (pinfunction "1_1") (pintype "passive"))
      (node (ref "R32") (pin "1") (pinfunction "1_1") (pintype "passive"))
      (node (ref "TEMP") (pin "2") (pinfunction "S_2") (pintype "passive"))
      (node (ref "U$11") (pin "1") (pinfunction "1_1") (pintype "passive"))
    )
    (net (code "67") (name "VCC") (class "Default")
      (node (ref "C11") (pin "2") (pinfunction "2_2") (pintype "passive"))
      (node (ref "C12") (pin "1") (pinfunction "1_1") (pintype "passive"))
      (node (ref "C13") (pin "1") (pinfunction "1_1") (pintype "passive"))
      (node (ref "C14") (pin "1") (pinfunction "1_1") (pintype "passive"))
      (node (ref "C19") (pin "2") (pinfunction "2_2") (pintype "passive"))
      (node (ref "C20") (pin "2") (pinfunction "2_2") (pintype "passive"))
      (node (ref "C21") (pin "2") (pinfunction "2_2") (pintype "passive"))
      (node (ref "C22") (pin "2") (pinfunction "2_2") (pintype "passive"))
      (node (ref "C23") (pin "2") (pinfunction "2_2") (pintype "passive"))
      (node (ref "C24") (pin "2") (pinfunction "2_2") (pintype "passive"))
      (node (ref "U$1") (pin "D1") (pinfunction "D_D1") (pintype "passive"))
      (node (ref "U$15") (pin "P$1") (pinfunction "P$1_P$1") (pintype "bidirectional"))
      (node (ref "U$4") (pin "D1") (pinfunction "D_D1") (pintype "passive"))
      (node (ref "U$5") (pin "D1") (pinfunction "D_D1") (pintype "passive"))
      (node (ref "U$7") (pin "P$29") (pinfunction "PVDD1_P$29") (pintype "bidirectional"))
      (node (ref "U$7") (pin "P$53") (pinfunction "PVDD2_P$53") (pintype "bidirectional"))
      (node (ref "U$7") (pin "P$54") (pinfunction "PVDD2(2)_P$54") (pintype "bidirectional"))
    )
    (net (code "68") (name "unconnected-(U$7-SS_TR-PadP$56)") (class "Default")
      (node (ref "U$7") (pin "P$56") (pinfunction "SS_TR_P$56") (pintype "bidirectional"))
    )
  )
)
